# RS-485_SN65HVD72DRBR.net
KiCad netlist of a schematic drawn in Altium Designer
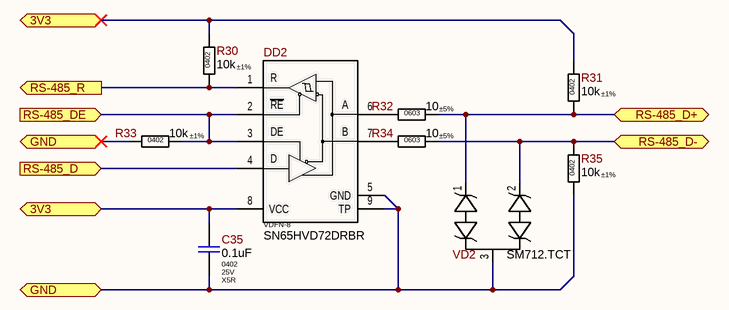
[diagram p0: RS-485_SN65HVD72DRBR.SchDoc]

(export (version "E")
  (design (tool "Eeschema 10.0.6"))
  (components
    (comp (ref "C35")
      (value "0.1uF")
      (footprint "C_CERAMIC_0402_HI")
      (description "100nF 25V X5R ±10% 0402 Ceramic Capacitor RoHS")
      (fields
        (field (name "PACKAGE") "0402")
        (field (name "VOLTAGE") "25V")
        (field (name "DIELECTRIC TYPE") "X5R")
        (field (name "PART NUMBER") "CL05A104KA5NNNC")
        (field (name "MANUFACTURER") "Samsung Electro-Mechanics")
      )
      (libsource (lib "EL.XXX.T01") (part "CL05A104KA5NNNC"))
    )
    (comp (ref "DD2")
      (value "SN65HVD72DRBR")
      (footprint "TI-SON8-65P300X100_HS")
      (description "3.3V 1/1 Transceiver Half RS422 Up to 250 kbps, RS485 With IEC ESD protection, SON-8")
      (fields
        (field (name "PACKAGE") "VDFN-8")
        (field (name "PART NUMBER") "SN65HVD72DRBR")
        (field (name "MANUFACTURER") "Texas Instruments")
      )
      (libsource (lib "EL.XXX.T01") (part "SN65HVD72DRBR"))
    )
    (comp (ref "R30")
      (value "10k")
      (footprint "R_ANY_CHIP_0402_MED")
      (description "10 kOhms ±1% 1/16W 0402 Thick Film Resistor")
      (fields
        (field (name "TOLERANCE") "±1%")
        (field (name "PACKAGE") "0402")
        (field (name "PART NUMBER") "RC0402FR-0710KL")
        (field (name "MANUFACTURER") "Yageo")
      )
      (libsource (lib "EL.XXX.T01") (part "RC0402FR-0710KL"))
    )
    (comp (ref "R31")
      (value "10k")
      (footprint "R_ANY_CHIP_0402_MED")
      (description "10 kOhms ±1% 1/16W 0402 Thick Film Resistor")
      (fields
        (field (name "TOLERANCE") "±1%")
        (field (name "PACKAGE") "0402")
        (field (name "PART NUMBER") "RC0402FR-0710KL")
        (field (name "MANUFACTURER") "Yageo")
      )
      (libsource (lib "EL.XXX.T01") (part "RC0402FR-0710KL"))
    )
    (comp (ref "R32")
      (value "10")
      (footprint "R_ANY_CHIP_0603_MED")
      (description "10 Ohms ±5%, 1/10W 0603 Thick Film Resistor")
      (fields
        (field (name "TOLERANCE") "±5%")
        (field (name "PACKAGE") "0603")
        (field (name "PART NUMBER") "RC0603JR-0710RL")
        (field (name "MANUFACTURER") "Yageo")
      )
      (libsource (lib "EL.XXX.T01") (part "RC0603JR-0710RL"))
    )
    (comp (ref "R33")
      (value "10k")
      (footprint "R_ANY_CHIP_0402_MED")
      (description "10 kOhms ±1% 1/16W 0402 Thick Film Resistor")
      (fields
        (field (name "TOLERANCE") "±1%")
        (field (name "PACKAGE") "0402")
        (field (name "PART NUMBER") "RC0402FR-0710KL")
        (field (name "MANUFACTURER") "Yageo")
      )
      (libsource (lib "EL.XXX.T01") (part "RC0402FR-0710KL"))
    )
    (comp (ref "R34")
      (value "10")
      (footprint "R_ANY_CHIP_0603_MED")
      (description "10 Ohms ±5%, 1/10W 0603 Thick Film Resistor")
      (fields
        (field (name "TOLERANCE") "±5%")
        (field (name "PACKAGE") "0603")
        (field (name "PART NUMBER") "RC0603JR-0710RL")
        (field (name "MANUFACTURER") "Yageo")
      )
      (libsource (lib "EL.XXX.T01") (part "RC0603JR-0710RL"))
    )
    (comp (ref "R35")
      (value "10k")
      (footprint "R_ANY_CHIP_0402_MED")
      (description "10 kOhms ±1% 1/16W 0402 Thick Film Resistor")
      (fields
        (field (name "TOLERANCE") "±1%")
        (field (name "PACKAGE") "0402")
        (field (name "PART NUMBER") "RC0402FR-0710KL")
        (field (name "MANUFACTURER") "Yageo")
      )
      (libsource (lib "EL.XXX.T01") (part "RC0402FR-0710KL"))
    )
    (comp (ref "VD2")
      (value "SM712.TCT")
      (footprint "SOT-23_MED")
      (description "TVS Diode 26V and 19V Clamp, 21A and 38A (8/20us) Ipp, SOT-23")
      (fields
        (field (name "PART NUMBER") "SM712.TCT")
        (field (name "MANUFACTURER") "Semtech")
        (field (name "VOLTAGE") "13.3V, 7.5V")
      )
      (libsource (lib "EL.XXX.T01") (part "SM712.TCT"))
    )
  )
  (nets
    (net (code "1") (name "/3V3") (class "Default")
      (node (ref "C35") (pin "1") (pinfunction "1_1") (pintype "passive"))
      (node (ref "DD2") (pin "8") (pinfunction "VCC_8") (pintype "passive"))
      (node (ref "R30") (pin "1") (pintype "passive"))
      (node (ref "R31") (pin "1") (pintype "passive"))
    )
    (net (code "2") (name "/GND") (class "Default")
      (node (ref "C35") (pin "2") (pinfunction "2_2") (pintype "passive"))
      (node (ref "DD2") (pin "5") (pinfunction "GND_5") (pintype "passive"))
      (node (ref "DD2") (pin "9") (pinfunction "TP_9") (pintype "passive"))
      (node (ref "R33") (pin "2") (pintype "passive"))
      (node (ref "R35") (pin "2") (pintype "passive"))
      (node (ref "VD2") (pin "3") (pintype "passive"))
    )
    (net (code "3") (name "/RS-485_D") (class "Default")
      (node (ref "DD2") (pin "4") (pinfunction "DI_4") (pintype "passive"))
    )
    (net (code "4") (name "/RS-485_D+") (class "Default")
      (node (ref "R31") (pin "2") (pintype "passive"))
      (node (ref "R32") (pin "2") (pintype "passive"))
      (node (ref "VD2") (pin "1") (pintype "passive"))
    )
    (net (code "5") (name "/RS-485_D-") (class "Default")
      (node (ref "R34") (pin "2") (pintype "passive"))
      (node (ref "R35") (pin "1") (pintype "passive"))
      (node (ref "VD2") (pin "2") (pintype "passive"))
    )
    (net (code "6") (name "/RS-485_DE") (class "Default")
      (node (ref "DD2") (pin "2") (pinfunction "~{RE}_2") (pintype "passive"))
      (node (ref "DD2") (pin "3") (pinfunction "DE_3") (pintype "passive"))
      (node (ref "R33") (pin "1") (pintype "passive"))
    )
    (net (code "7") (name "/RS-485_R") (class "Default")
      (node (ref "DD2") (pin "1") (pinfunction "RO_1") (pintype "passive"))
      (node (ref "R30") (pin "2") (pintype "passive"))
    )
    (net (code "8") (name "Net-(DD2-A)") (class "Default")
      (node (ref "DD2") (pin "6") (pinfunction "A_6") (pintype "passive"))
      (node (ref "R32") (pin "1") (pintype "passive"))
    )
    (net (code "9") (name "Net-(DD2-B)") (class "Default")
      (node (ref "DD2") (pin "7") (pinfunction "B_7") (pintype "passive"))
      (node (ref "R34") (pin "1") (pintype "passive"))
    )
  )
)
